# valve_board-OSH2.net
KiCad netlist of a schematic drawn in EAGLE
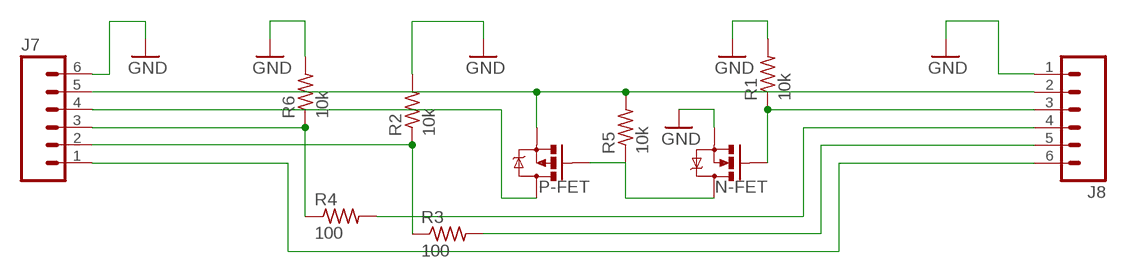
[diagram p0: schematic, sheet 1]

(export (version "E")
  (design (tool "Eeschema 10.0.6"))
  (components
    (comp (ref "J7")
      (value "M06LOCK_LONGPADS")
      (footprint "eagle-import:1X06_LOCK_LONGPADS")
      (libsource (lib "eagle-import") (part "M06LOCK_LONGPADS"))
    )
    (comp (ref "J8")
      (value "M06LOCK_LONGPADS")
      (footprint "eagle-import:1X06_LOCK_LONGPADS")
      (libsource (lib "eagle-import") (part "M06LOCK_LONGPADS"))
    )
    (comp (ref "N-FET")
      (value "MOSFET-NCHANNELFQP30N06L")
      (footprint "eagle-import:TO220V")
      (libsource (lib "eagle-import") (part "MOSFET-NCHANNELFQP30N06L"))
    )
    (comp (ref "P-FET")
      (value "MOSFET-PCHANNELFQP27P06")
      (footprint "eagle-import:TO220V")
      (libsource (lib "eagle-import") (part "MOSFET-PCHANNELFQP27P06"))
    )
    (comp (ref "R1")
      (value "10k")
      (footprint "eagle-import:0207_10")
      (libsource (lib "eagle-import") (part "R-US_0207/10"))
    )
    (comp (ref "R2")
      (value "10k")
      (footprint "eagle-import:0207_10")
      (libsource (lib "eagle-import") (part "R-US_0207/10"))
    )
    (comp (ref "R3")
      (value "100")
      (footprint "eagle-import:0207_10")
      (libsource (lib "eagle-import") (part "R-US_0207/10"))
    )
    (comp (ref "R4")
      (value "100")
      (footprint "eagle-import:0207_10")
      (libsource (lib "eagle-import") (part "R-US_0207/10"))
    )
    (comp (ref "R5")
      (value "10k")
      (footprint "eagle-import:0207_10")
      (libsource (lib "eagle-import") (part "R-US_0207/10"))
    )
    (comp (ref "R6")
      (value "10k")
      (footprint "eagle-import:0207_10")
      (libsource (lib "eagle-import") (part "R-US_0207/10"))
    )
  )
  (nets
    (net (code "1") (name "GND") (class "Default")
      (node (ref "J7") (pin "6") (pinfunction "6_6") (pintype "passive"))
      (node (ref "J8") (pin "1") (pinfunction "1_1") (pintype "passive"))
      (node (ref "N-FET") (pin "3") (pinfunction "S_3") (pintype "passive"))
      (node (ref "R1") (pin "2") (pinfunction "2_2") (pintype "passive"))
      (node (ref "R2") (pin "2") (pinfunction "2_2") (pintype "passive"))
      (node (ref "R6") (pin "2") (pinfunction "2_2") (pintype "passive"))
    )
    (net (code "2") (name "Net-(J7-Pad1)") (class "Default")
      (node (ref "J7") (pin "1") (pinfunction "1_1") (pintype "passive"))
      (node (ref "J8") (pin "6") (pinfunction "6_6") (pintype "passive"))
    )
    (net (code "3") (name "Net-(J7-Pad2)") (class "Default")
      (node (ref "J7") (pin "2") (pinfunction "2_2") (pintype "passive"))
      (node (ref "R2") (pin "1") (pinfunction "1_1") (pintype "passive"))
      (node (ref "R3") (pin "1") (pinfunction "1_1") (pintype "passive"))
    )
    (net (code "4") (name "Net-(J7-Pad3)") (class "Default")
      (node (ref "J7") (pin "3") (pinfunction "3_3") (pintype "passive"))
      (node (ref "R4") (pin "1") (pinfunction "1_1") (pintype "passive"))
      (node (ref "R6") (pin "1") (pinfunction "1_1") (pintype "passive"))
    )
    (net (code "5") (name "Net-(J8-Pad4)") (class "Default")
      (node (ref "J8") (pin "4") (pinfunction "4_4") (pintype "passive"))
      (node (ref "R4") (pin "2") (pinfunction "2_2") (pintype "passive"))
    )
    (net (code "6") (name "Net-(J8-Pad5)") (class "Default")
      (node (ref "J8") (pin "5") (pinfunction "5_5") (pintype "passive"))
      (node (ref "R3") (pin "2") (pinfunction "2_2") (pintype "passive"))
    )
    (net (code "7") (name "Net-(N-FET-D)") (class "Default")
      (node (ref "N-FET") (pin "2") (pinfunction "D_2") (pintype "passive"))
      (node (ref "P-FET") (pin "1") (pinfunction "G_1") (pintype "passive"))
      (node (ref "R5") (pin "1") (pinfunction "1_1") (pintype "passive"))
    )
    (net (code "8") (name "Net-(N-FET-G)") (class "Default")
      (node (ref "J8") (pin "3") (pinfunction "3_3") (pintype "passive"))
      (node (ref "N-FET") (pin "1") (pinfunction "G_1") (pintype "passive"))
      (node (ref "R1") (pin "1") (pinfunction "1_1") (pintype "passive"))
    )
    (net (code "9") (name "Net-(P-FET-D)") (class "Default")
      (node (ref "J7") (pin "4") (pinfunction "4_4") (pintype "passive"))
      (node (ref "P-FET") (pin "2") (pinfunction "D_2") (pintype "passive"))
    )
    (net (code "10") (name "Net-(P-FET-S)") (class "Default")
      (node (ref "J7") (pin "5") (pinfunction "5_5") (pintype "passive"))
      (node (ref "J8") (pin "2") (pinfunction "2_2") (pintype "passive"))
      (node (ref "P-FET") (pin "3") (pinfunction "S_3") (pintype "passive"))
      (node (ref "R5") (pin "2") (pinfunction "2_2") (pintype "passive"))
    )
  )
)
